# Gas_Sensor_Schematic.net
KiCad netlist of a schematic drawn in Altium Designer
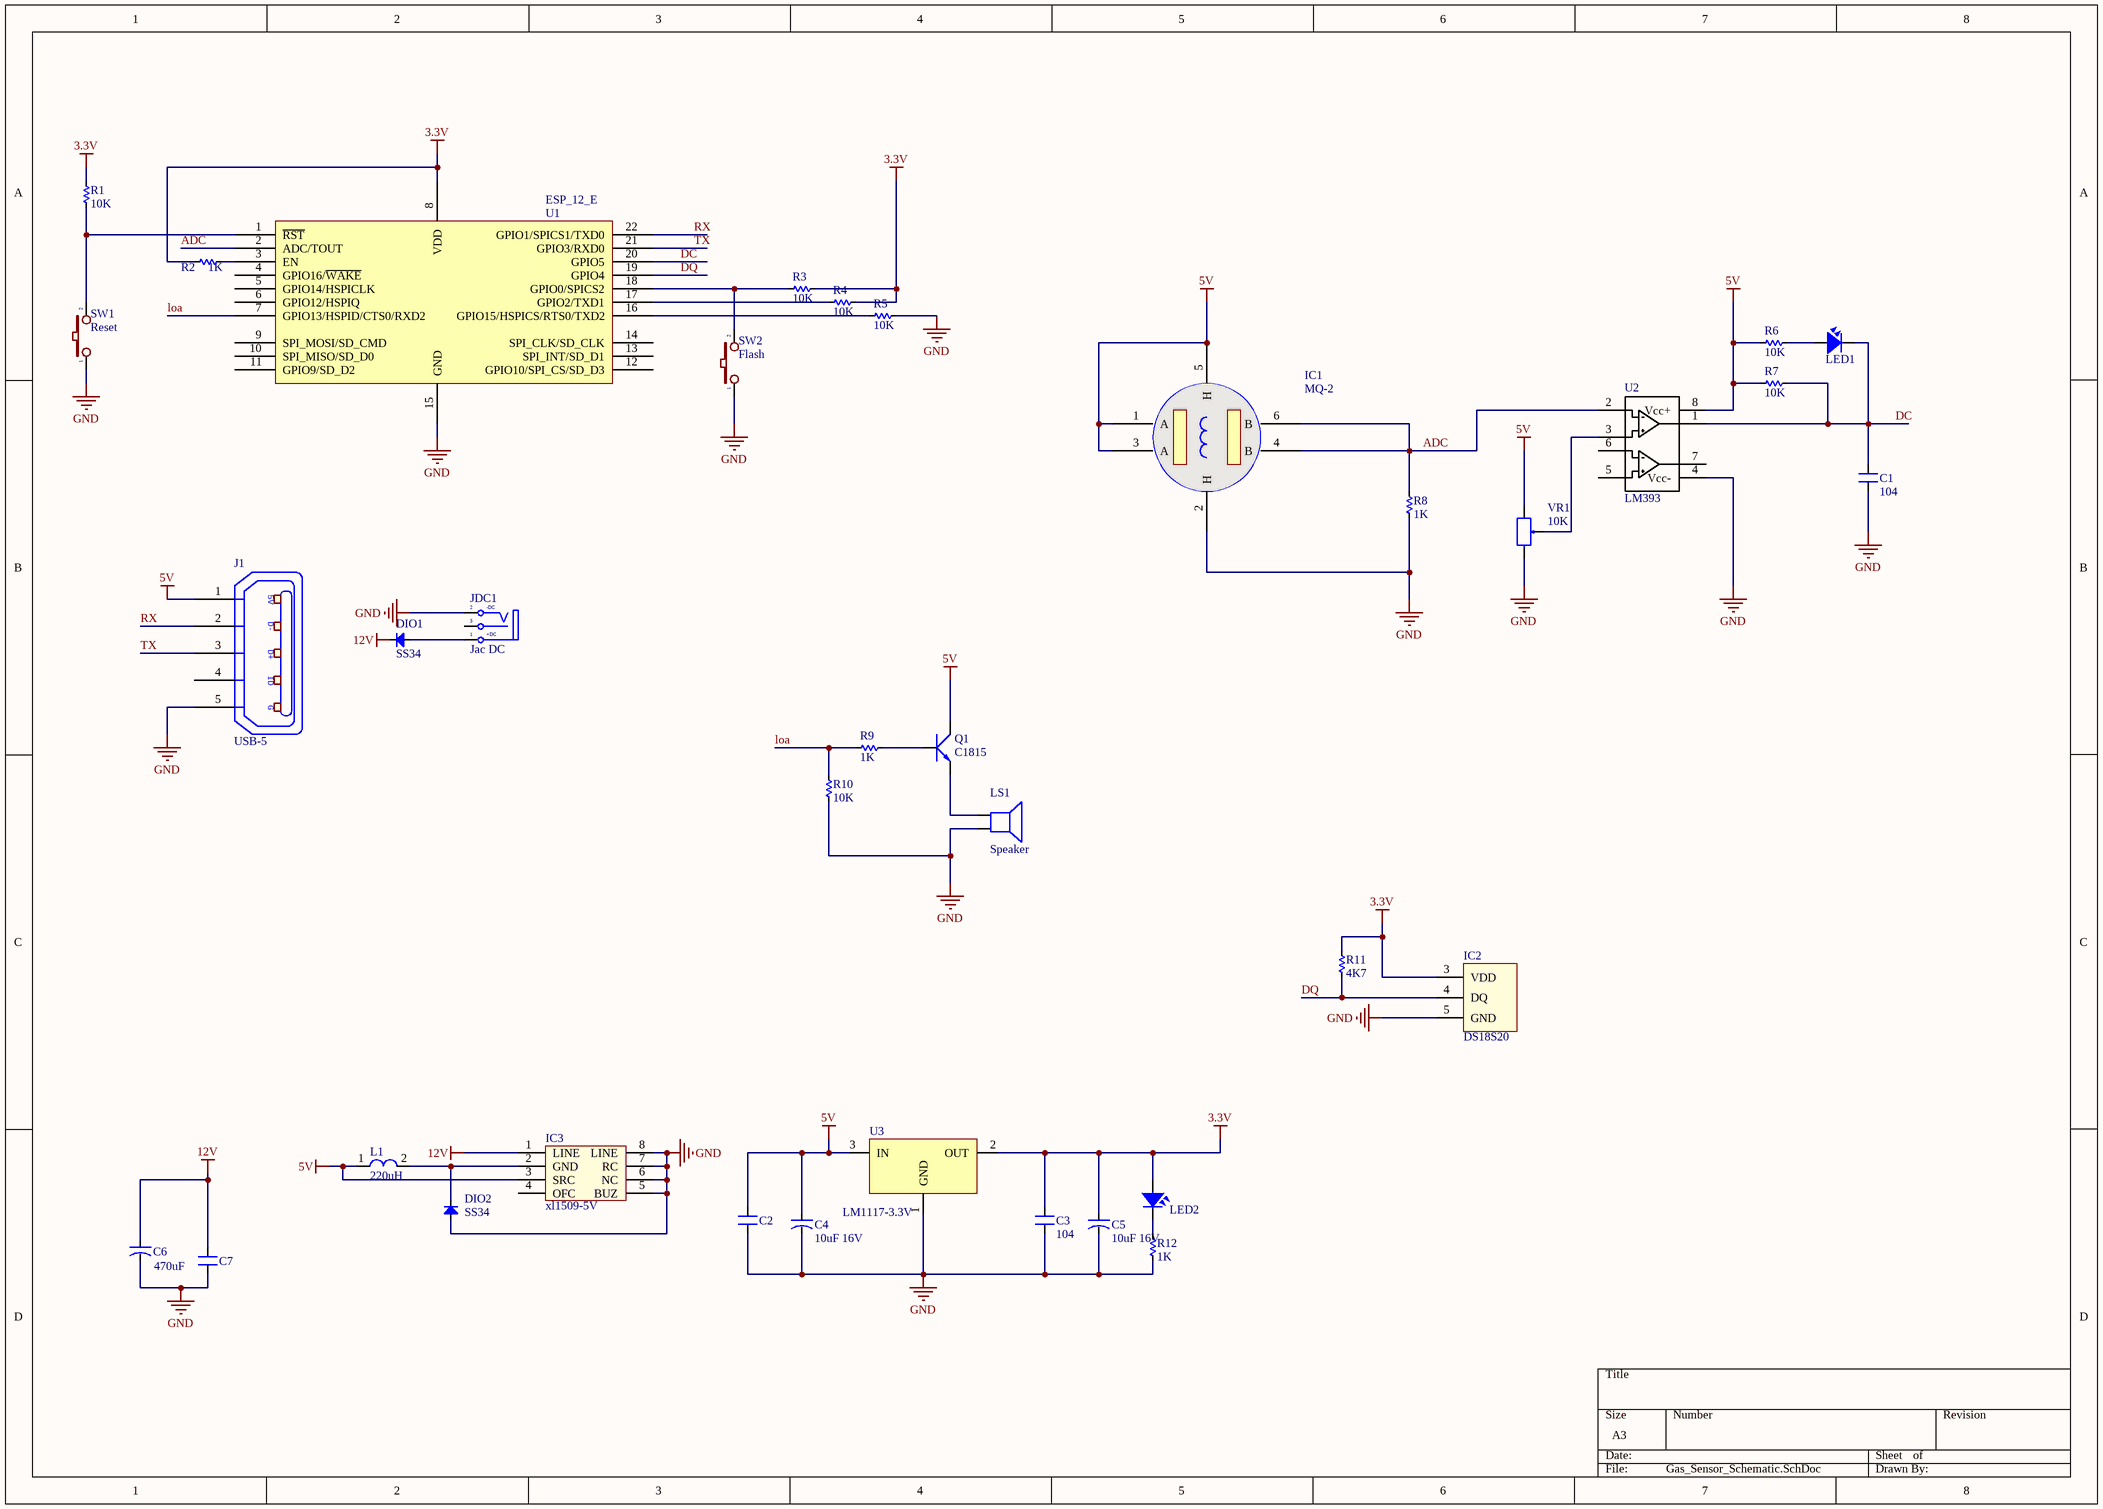
[diagram p0: Gas_Sensor_Schematic.SchDoc]

(export (version "E")
  (design (tool "Eeschema 10.0.6"))
  (components
    (comp (ref "C1")
      (value "104")
      (footprint "SM-CAP-0805")
      (fields (field (name "DESIGNED BY") "VanDungEvn"))
      (libsource (lib "electronicvn-library1") (part "CN"))
    )
    (comp (ref "C2")
      (value "104")
      (footprint "SM-CAP-0805")
      (fields (field (name "DESIGNED BY") "VanDungEvn"))
      (libsource (lib "electronicvn-library1") (part "CN"))
    )
    (comp (ref "C3")
      (value "104")
      (footprint "SM-CAP-0805")
      (fields (field (name "DESIGNED BY") "VanDungEvn"))
      (libsource (lib "electronicvn-library1") (part "CN"))
    )
    (comp (ref "C4")
      (value "10uF 16V")
      (footprint "CAP-ALU-SMD-4.5x5x1.4")
      (description "Polarized Capacitor (Axial)")
      (fields (field (name "PUBLISHER") "Altium Limited"))
      (libsource (lib "LIBTanCN") (part "CN-ALU-SMD"))
    )
    (comp (ref "C5")
      (value "10uF 16V")
      (footprint "CAP-ALU-SMD-4.5x5x1.4")
      (description "Polarized Capacitor (Axial)")
      (fields (field (name "PUBLISHER") "Altium Limited"))
      (libsource (lib "LIBTanCN") (part "CN-ALU-SMD"))
    )
    (comp (ref "C6")
      (value "470uF")
      (footprint "CAP-ALU-SMD-6.3x7.7x2.2")
      (description "Polarized Capacitor (Axial)")
      (fields (field (name "PUBLISHER") "Altium Limited"))
      (libsource (lib "LIBTanCN") (part "CN-ALU-SMD"))
    )
    (comp (ref "C7")
      (value "104")
      (footprint "SM-CAP-0805")
      (fields (field (name "DESIGNED BY") "VanDungEvn"))
      (libsource (lib "electronicvn-library1") (part "CN"))
    )
    (comp (ref "DIO1")
      (value "SS34")
      (footprint "DIO-SMD-106")
      (description "Default Diode")
      (fields (field (name "PUBLISHER") "Altium Limited"))
      (libsource (lib "LIBRARY") (part "Diode SMD"))
    )
    (comp (ref "DIO2")
      (value "SS34")
      (footprint "DIO-SMD-106")
      (description "Default Diode")
      (fields (field (name "PUBLISHER") "Altium Limited"))
      (libsource (lib "LIBRARY") (part "Diode SMD"))
    )
    (comp (ref "IC1")
      (value "MQ-2")
      (footprint "heromap:MQ-2")
      (description "MQ-2 GAS SENSOR")
      (libsource (lib "heromap") (part "MQ-2"))
    )
    (comp (ref "IC2")
      (value "DS18S20")
      (footprint "DS18S20")
      (description "High Precision  1-Wire® Digital Thermometer")
      (libsource (lib "LIBTanCN") (part "DS18S20"))
    )
    (comp (ref "IC3")
      (value "xl1509-5V")
      (footprint "SO-8")
      (description "Electronic Two-Tone Ringer")
      (libsource (lib "LIBTanCN") (part "LS1240A"))
    )
    (comp (ref "J1")
      (value "USB-5")
      (footprint "USB-M1")
      (fields
        (field (name "MANUFACTURER") "FCI")
        (field (name "MANUFACTURER PART NUMBER") "10118193-0001LF")
        (field (name ".CREATOR") "MM")
        (field (name ".CHECKED PCB") "RF")
        (field (name ".CHECKED SCH") "MM")
      )
      (libsource (lib "LIBRARY") (part "USB-5"))
    )
    (comp (ref "JDC1")
      (value "Jac DC")
      (footprint "DC3")
      (description "Jac DC input")
      (libsource (lib "LIBRARY") (part "DCIN"))
    )
    (comp (ref "L1")
      (value "220uH")
      (footprint "L-SMD-M-7.3x4.5")
      (fields
        (field (name "PARTNO") "78477010")
        (field (name "MANUFACTURER") "Wurth Elektronik")
        (field (name "CREATED BY") "Baojun Chen")
      )
      (libsource (lib "LIBRARY") (part "L-SMD-1"))
    )
    (comp (ref "LED1") (value "LED") (footprint "LED-0805-Blue") (libsource (lib "LIBRARY") (part "LED SMD")))
    (comp (ref "LED2") (value "LED") (footprint "LED-0805-Blue") (libsource (lib "LIBRARY") (part "LED SMD")))
    (comp (ref "LS1")
      (value "Speaker")
      (footprint "SPEAKER")
      (description "Loudspeaker")
      (fields (field (name "PUBLISHER") "Altium Limited"))
      (libsource (lib "LIBRARY") (part "Speaker"))
    )
    (comp (ref "Q1")
      (value "C1815")
      (footprint "SOT23B")
      (description "NPN 600mW, ECB")
      (libsource (lib "electronicvn-library1") (part "C1815"))
    )
    (comp (ref "R1")
      (value "10K")
      (footprint "RES-SMD-0805")
      (description "Resistor")
      (fields
        (field (name "MANUFACTURER") "Generic Components")
        (field (name "PUBLISHER") "Altium Hobart Technology Centre")
      )
      (libsource (lib "LIBRARY") (part "Res-SMD"))
    )
    (comp (ref "R2")
      (value "1K")
      (footprint "RES-SMD-0805")
      (description "Resistor")
      (fields
        (field (name "MANUFACTURER") "Generic Components")
        (field (name "PUBLISHER") "Altium Hobart Technology Centre")
      )
      (libsource (lib "LIBRARY") (part "Res-SMD"))
    )
    (comp (ref "R3")
      (value "10K")
      (footprint "RES-SMD-0805")
      (description "Resistor")
      (fields
        (field (name "MANUFACTURER") "Generic Components")
        (field (name "PUBLISHER") "Altium Hobart Technology Centre")
      )
      (libsource (lib "LIBRARY") (part "Res-SMD"))
    )
    (comp (ref "R4")
      (value "10K")
      (footprint "RES-SMD-0805")
      (description "Resistor")
      (fields
        (field (name "MANUFACTURER") "Generic Components")
        (field (name "PUBLISHER") "Altium Hobart Technology Centre")
      )
      (libsource (lib "LIBRARY") (part "Res-SMD"))
    )
    (comp (ref "R5")
      (value "10K")
      (footprint "RES-SMD-0805")
      (description "Resistor")
      (fields
        (field (name "MANUFACTURER") "Generic Components")
        (field (name "PUBLISHER") "Altium Hobart Technology Centre")
      )
      (libsource (lib "LIBRARY") (part "Res-SMD"))
    )
    (comp (ref "R6")
      (value "10K")
      (footprint "RES-SMD-0805")
      (description "Resistor")
      (fields
        (field (name "MANUFACTURER") "Generic Components")
        (field (name "PUBLISHER") "Altium Hobart Technology Centre")
      )
      (libsource (lib "LIBRARY") (part "Res-SMD"))
    )
    (comp (ref "R7")
      (value "10K")
      (footprint "RES-SMD-0805")
      (description "Resistor")
      (fields
        (field (name "MANUFACTURER") "Generic Components")
        (field (name "PUBLISHER") "Altium Hobart Technology Centre")
      )
      (libsource (lib "LIBRARY") (part "Res-SMD"))
    )
    (comp (ref "R8")
      (value "1K")
      (footprint "RES-SMD-0805")
      (description "Resistor")
      (fields
        (field (name "MANUFACTURER") "Generic Components")
        (field (name "PUBLISHER") "Altium Hobart Technology Centre")
      )
      (libsource (lib "LIBRARY") (part "Res-SMD"))
    )
    (comp (ref "R9")
      (value "1K")
      (footprint "RES-SMD-0805")
      (description "Resistor")
      (fields
        (field (name "MANUFACTURER") "Generic Components")
        (field (name "PUBLISHER") "Altium Hobart Technology Centre")
      )
      (libsource (lib "LIBRARY") (part "Res-SMD"))
    )
    (comp (ref "R10")
      (value "10K")
      (footprint "RES-SMD-0805")
      (description "Resistor")
      (fields
        (field (name "MANUFACTURER") "Generic Components")
        (field (name "PUBLISHER") "Altium Hobart Technology Centre")
      )
      (libsource (lib "LIBRARY") (part "Res-SMD"))
    )
    (comp (ref "R11")
      (value "4K7")
      (footprint "RES-SMD-0805")
      (description "Resistor")
      (fields
        (field (name "MANUFACTURER") "Generic Components")
        (field (name "PUBLISHER") "Altium Hobart Technology Centre")
      )
      (libsource (lib "LIBRARY") (part "Res-SMD"))
    )
    (comp (ref "R12")
      (value "1K")
      (footprint "RES-SMD-0805")
      (description "Resistor")
      (fields
        (field (name "MANUFACTURER") "Generic Components")
        (field (name "PUBLISHER") "Altium Hobart Technology Centre")
      )
      (libsource (lib "LIBRARY") (part "Res-SMD"))
    )
    (comp (ref "SW1")
      (value "Reset")
      (footprint "SW1-SMD")
      (description "Switch button 2 pin")
      (libsource (lib "LIBRARY") (part "SW2"))
    )
    (comp (ref "SW2")
      (value "Flash")
      (footprint "SW-DIP1")
      (description "Switch button 2 pin")
      (libsource (lib "LIBRARY") (part "SW2"))
    )
    (comp (ref "U1")
      (value "ESP_12_E")
      (footprint "ESP_12_E")
      (description "ESP-12 Wi-Fi Module by AI-Thinker")
      (libsource (lib "ESP8266") (part "ESP_12_E"))
    )
    (comp (ref "U2")
      (value "LM393")
      (footprint "SO8")
      (description "IC DUAL COMPARATOR")
      (libsource (lib "LIBRARY") (part "LM393"))
    )
    (comp (ref "U3")
      (value "LM1117-3.3V")
      (footprint "SOT223")
      (description "800mA Low-Dropout Linear Regulator")
      (fields (field (name "CREATOR") "Nguyen Ba Bien"))
      (libsource (lib "LIBRARY") (part "LM1117"))
    )
    (comp (ref "VR1")
      (value "10K")
      (footprint "VR")
      (description "Var Resistor")
      (libsource (lib "LIBTanCN") (part "VR"))
    )
  )
  (nets
    (net (code "1") (name "/ADC") (class "Default")
      (node (ref "IC1") (pin "4") (pinfunction "B_4") (pintype "passive"))
      (node (ref "IC1") (pin "6") (pinfunction "B_6") (pintype "passive"))
      (node (ref "R8") (pin "1") (pinfunction "1_1") (pintype "passive"))
      (node (ref "U1") (pin "2") (pinfunction "ADC/TOUT_2") (pintype "passive"))
      (node (ref "U2") (pin "2") (pintype "passive"))
    )
    (net (code "2") (name "/DC") (class "Default")
      (node (ref "C1") (pin "2") (pinfunction "2_2") (pintype "passive"))
      (node (ref "LED1") (pin "2") (pinfunction "2_2") (pintype "passive"))
      (node (ref "R7") (pin "2") (pinfunction "2_2") (pintype "passive"))
      (node (ref "U1") (pin "20") (pinfunction "GPIO5_20") (pintype "passive"))
      (node (ref "U2") (pin "1") (pintype "passive"))
    )
    (net (code "3") (name "/DQ") (class "Default")
      (node (ref "IC2") (pin "4") (pinfunction "DQ_4") (pintype "passive"))
      (node (ref "R11") (pin "2") (pinfunction "2_2") (pintype "passive"))
      (node (ref "U1") (pin "19") (pinfunction "GPIO4_19") (pintype "passive"))
    )
    (net (code "4") (name "/RX") (class "Default")
      (node (ref "J1") (pin "2") (pinfunction "P2_2") (pintype "passive"))
      (node (ref "U1") (pin "22") (pinfunction "GPIO1/SPICS1/TXD0_22") (pintype "passive"))
    )
    (net (code "5") (name "/TX") (class "Default")
      (node (ref "J1") (pin "3") (pinfunction "P3_3") (pintype "passive"))
      (node (ref "U1") (pin "21") (pinfunction "GPIO3/RXD0_21") (pintype "passive"))
    )
    (net (code "6") (name "/loa") (class "Default")
      (node (ref "R10") (pin "1") (pinfunction "1_1") (pintype "passive"))
      (node (ref "R9") (pin "2") (pinfunction "2_2") (pintype "passive"))
      (node (ref "U1") (pin "7") (pinfunction "GPIO13/HSPID/CTS0/RXD2_7") (pintype "passive"))
    )
    (net (code "7") (name "3.3V") (class "Default")
      (node (ref "C3") (pin "2") (pinfunction "2_2") (pintype "passive"))
      (node (ref "C5") (pin "1") (pinfunction "1_1") (pintype "passive"))
      (node (ref "IC2") (pin "3") (pinfunction "VDD_3") (pintype "passive"))
      (node (ref "LED2") (pin "1") (pinfunction "1_1") (pintype "passive"))
      (node (ref "R1") (pin "1") (pinfunction "1_1") (pintype "passive"))
      (node (ref "R11") (pin "1") (pinfunction "1_1") (pintype "passive"))
      (node (ref "R2") (pin "2") (pinfunction "2_2") (pintype "passive"))
      (node (ref "R3") (pin "1") (pinfunction "1_1") (pintype "passive"))
      (node (ref "R4") (pin "1") (pinfunction "1_1") (pintype "passive"))
      (node (ref "U1") (pin "8") (pinfunction "VDD_8") (pintype "passive"))
      (node (ref "U3") (pin "2") (pinfunction "OUT_2") (pintype "passive"))
    )
    (net (code "8") (name "5V") (class "Default")
      (node (ref "C2") (pin "2") (pinfunction "2_2") (pintype "passive"))
      (node (ref "C4") (pin "1") (pinfunction "1_1") (pintype "passive"))
      (node (ref "IC1") (pin "1") (pinfunction "A_1") (pintype "passive"))
      (node (ref "IC1") (pin "3") (pinfunction "A_3") (pintype "passive"))
      (node (ref "IC1") (pin "5") (pinfunction "H_5") (pintype "passive"))
      (node (ref "IC3") (pin "3") (pinfunction "SRC_3") (pintype "passive"))
      (node (ref "J1") (pin "1") (pinfunction "P1_1") (pintype "passive"))
      (node (ref "L1") (pin "1") (pinfunction "1_1") (pintype "passive"))
      (node (ref "Q1") (pin "2") (pinfunction "C_2") (pintype "passive"))
      (node (ref "R6") (pin "1") (pinfunction "1_1") (pintype "passive"))
      (node (ref "R7") (pin "1") (pinfunction "1_1") (pintype "passive"))
      (node (ref "U2") (pin "8") (pinfunction "Vcc+_8") (pintype "passive"))
      (node (ref "U3") (pin "3") (pinfunction "IN_3") (pintype "passive"))
      (node (ref "VR1") (pin "1") (pinfunction "1_1") (pintype "passive"))
    )
    (net (code "9") (name "12V") (class "Default")
      (node (ref "C6") (pin "1") (pinfunction "1_1") (pintype "passive"))
      (node (ref "C7") (pin "2") (pinfunction "2_2") (pintype "passive"))
      (node (ref "DIO1") (pin "2") (pinfunction "K_2") (pintype "passive"))
      (node (ref "IC3") (pin "1") (pinfunction "LINE_1") (pintype "passive"))
    )
    (net (code "10") (name "GND") (class "Default")
      (node (ref "C1") (pin "1") (pinfunction "1_1") (pintype "passive"))
      (node (ref "C2") (pin "1") (pinfunction "1_1") (pintype "passive"))
      (node (ref "C3") (pin "1") (pinfunction "1_1") (pintype "passive"))
      (node (ref "C4") (pin "2") (pinfunction "2_2") (pintype "passive"))
      (node (ref "C5") (pin "2") (pinfunction "2_2") (pintype "passive"))
      (node (ref "C6") (pin "2") (pinfunction "2_2") (pintype "passive"))
      (node (ref "C7") (pin "1") (pinfunction "1_1") (pintype "passive"))
      (node (ref "DIO2") (pin "1") (pinfunction "A_1") (pintype "passive"))
      (node (ref "IC1") (pin "2") (pinfunction "H_2") (pintype "passive"))
      (node (ref "IC2") (pin "5") (pinfunction "GND_5") (pintype "passive"))
      (node (ref "IC3") (pin "5") (pinfunction "BUZ_5") (pintype "passive"))
      (node (ref "IC3") (pin "6") (pinfunction "NC_6") (pintype "passive"))
      (node (ref "IC3") (pin "7") (pinfunction "RC_7") (pintype "passive"))
      (node (ref "IC3") (pin "8") (pinfunction "LINE_8") (pintype "passive"))
      (node (ref "J1") (pin "5") (pinfunction "P5_5") (pintype "passive"))
      (node (ref "JDC1") (pin "2") (pinfunction "TN_2") (pintype "passive"))
      (node (ref "LS1") (pin "2") (pinfunction "2_2") (pintype "passive"))
      (node (ref "R10") (pin "2") (pinfunction "2_2") (pintype "passive"))
      (node (ref "R12") (pin "2") (pinfunction "2_2") (pintype "passive"))
      (node (ref "R5") (pin "1") (pinfunction "1_1") (pintype "passive"))
      (node (ref "R8") (pin "2") (pinfunction "2_2") (pintype "passive"))
      (node (ref "SW1") (pin "1") (pinfunction "1_1") (pintype "passive"))
      (node (ref "SW2") (pin "1") (pinfunction "1_1") (pintype "passive"))
      (node (ref "U1") (pin "15") (pinfunction "GND_15") (pintype "passive"))
      (node (ref "U2") (pin "4") (pinfunction "Vcc-_4") (pintype "passive"))
      (node (ref "U3") (pin "1") (pinfunction "GND_1") (pintype "passive"))
      (node (ref "VR1") (pin "3") (pinfunction "3_3") (pintype "passive"))
    )
    (net (code "11") (name "Net-(DIO1-A)") (class "Default")
      (node (ref "DIO1") (pin "1") (pinfunction "A_1") (pintype "passive"))
      (node (ref "JDC1") (pin "1") (pinfunction "T_1") (pintype "passive"))
    )
    (net (code "12") (name "Net-(DIO2-K)") (class "Default")
      (node (ref "DIO2") (pin "2") (pinfunction "K_2") (pintype "passive"))
      (node (ref "IC3") (pin "2") (pinfunction "GND_2") (pintype "passive"))
      (node (ref "L1") (pin "2") (pinfunction "2_2") (pintype "passive"))
    )
    (net (code "13") (name "Net-(LED1-Pad1)") (class "Default")
      (node (ref "LED1") (pin "1") (pinfunction "1_1") (pintype "passive"))
      (node (ref "R6") (pin "2") (pinfunction "2_2") (pintype "passive"))
    )
    (net (code "14") (name "Net-(LED2-Pad2)") (class "Default")
      (node (ref "LED2") (pin "2") (pinfunction "2_2") (pintype "passive"))
      (node (ref "R12") (pin "1") (pinfunction "1_1") (pintype "passive"))
    )
    (net (code "15") (name "Net-(Q1-B)") (class "Default")
      (node (ref "Q1") (pin "3") (pinfunction "B_3") (pintype "passive"))
      (node (ref "R9") (pin "1") (pinfunction "1_1") (pintype "passive"))
    )
    (net (code "16") (name "Net-(Q1-E)") (class "Default")
      (node (ref "LS1") (pin "1") (pinfunction "1_1") (pintype "passive"))
      (node (ref "Q1") (pin "1") (pinfunction "E_1") (pintype "passive"))
    )
    (net (code "17") (name "Net-(U1-EN)") (class "Default")
      (node (ref "R2") (pin "1") (pinfunction "1_1") (pintype "passive"))
      (node (ref "U1") (pin "3") (pinfunction "EN_3") (pintype "passive"))
    )
    (net (code "18") (name "Net-(U1-GPIO0{slash}SPICS2)") (class "Default")
      (node (ref "R3") (pin "2") (pinfunction "2_2") (pintype "passive"))
      (node (ref "SW2") (pin "2") (pinfunction "2_2") (pintype "passive"))
      (node (ref "U1") (pin "18") (pinfunction "GPIO0/SPICS2_18") (pintype "passive"))
    )
    (net (code "19") (name "Net-(U1-GPIO2{slash}TXD1)") (class "Default")
      (node (ref "R4") (pin "2") (pinfunction "2_2") (pintype "passive"))
      (node (ref "U1") (pin "17") (pinfunction "GPIO2/TXD1_17") (pintype "passive"))
    )
    (net (code "20") (name "Net-(U1-GPIO15{slash}HSPICS{slash}RTS0{slash}TXD2)") (class "Default")
      (node (ref "R5") (pin "2") (pinfunction "2_2") (pintype "passive"))
      (node (ref "U1") (pin "16") (pinfunction "GPIO15/HSPICS/RTS0/TXD2_16") (pintype "passive"))
    )
    (net (code "21") (name "Net-(U1-~{RST})") (class "Default")
      (node (ref "R1") (pin "2") (pinfunction "2_2") (pintype "passive"))
      (node (ref "SW1") (pin "2") (pinfunction "2_2") (pintype "passive"))
      (node (ref "U1") (pin "1") (pinfunction "~{RST}_1") (pintype "passive"))
    )
    (net (code "22") (name "Net-(U2-Pad3)") (class "Default")
      (node (ref "U2") (pin "3") (pintype "passive"))
      (node (ref "VR1") (pin "2") (pinfunction "2_2") (pintype "passive"))
    )
    (net (code "23") (name "unconnected-(IC3-OFC-Pad4)") (class "Default")
      (node (ref "IC3") (pin "4") (pinfunction "OFC_4") (pintype "passive"))
    )
    (net (code "24") (name "unconnected-(J1-P4-Pad4)") (class "Default")
      (node (ref "J1") (pin "4") (pinfunction "P4_4") (pintype "passive"))
    )
    (net (code "25") (name "unconnected-(JDC1-S-Pad3)") (class "Default")
      (node (ref "JDC1") (pin "3") (pinfunction "S_3") (pintype "power_in"))
    )
    (net (code "26") (name "unconnected-(U1-GPIO9{slash}SD_D2-Pad11)") (class "Default")
      (node (ref "U1") (pin "11") (pinfunction "GPIO9/SD_D2_11") (pintype "passive"))
    )
    (net (code "27") (name "unconnected-(U1-GPIO10{slash}SPI_CS{slash}SD_D3-Pad12)") (class "Default")
      (node (ref "U1") (pin "12") (pinfunction "GPIO10/SPI_CS/SD_D3_12") (pintype "passive"))
    )
    (net (code "28") (name "unconnected-(U1-GPIO12{slash}HSPIQ-Pad6)") (class "Default")
      (node (ref "U1") (pin "6") (pinfunction "GPIO12/HSPIQ_6") (pintype "passive"))
    )
    (net (code "29") (name "unconnected-(U1-GPIO14{slash}HSPICLK-Pad5)") (class "Default")
      (node (ref "U1") (pin "5") (pinfunction "GPIO14/HSPICLK_5") (pintype "passive"))
    )
    (net (code "30") (name "unconnected-(U1-GPIO16{slash}~{WAKE}-Pad4)") (class "Default")
      (node (ref "U1") (pin "4") (pinfunction "GPIO16/~{WAKE}_4") (pintype "passive"))
    )
    (net (code "31") (name "unconnected-(U1-SPI_CLK{slash}SD_CLK-Pad14)") (class "Default")
      (node (ref "U1") (pin "14") (pinfunction "SPI_CLK/SD_CLK_14") (pintype "passive"))
    )
    (net (code "32") (name "unconnected-(U1-SPI_INT{slash}SD_D1-Pad13)") (class "Default")
      (node (ref "U1") (pin "13") (pinfunction "SPI_INT/SD_D1_13") (pintype "passive"))
    )
    (net (code "33") (name "unconnected-(U1-SPI_MISO{slash}SD_D0-Pad10)") (class "Default")
      (node (ref "U1") (pin "10") (pinfunction "SPI_MISO/SD_D0_10") (pintype "passive"))
    )
    (net (code "34") (name "unconnected-(U1-SPI_MOSI{slash}SD_CMD-Pad9)") (class "Default")
      (node (ref "U1") (pin "9") (pinfunction "SPI_MOSI/SD_CMD_9") (pintype "passive"))
    )
    (net (code "35") (name "unconnected-(U2-Pad5)") (class "Default")
      (node (ref "U2") (pin "5") (pintype "passive"))
    )
    (net (code "36") (name "unconnected-(U2-Pad6)") (class "Default")
      (node (ref "U2") (pin "6") (pintype "passive"))
    )
    (net (code "37") (name "unconnected-(U2-Pad7)") (class "Default")
      (node (ref "U2") (pin "7") (pintype "passive"))
    )
  )
)
